# thermostat-2layer-v1.net
KiCad netlist of a schematic drawn in EAGLE
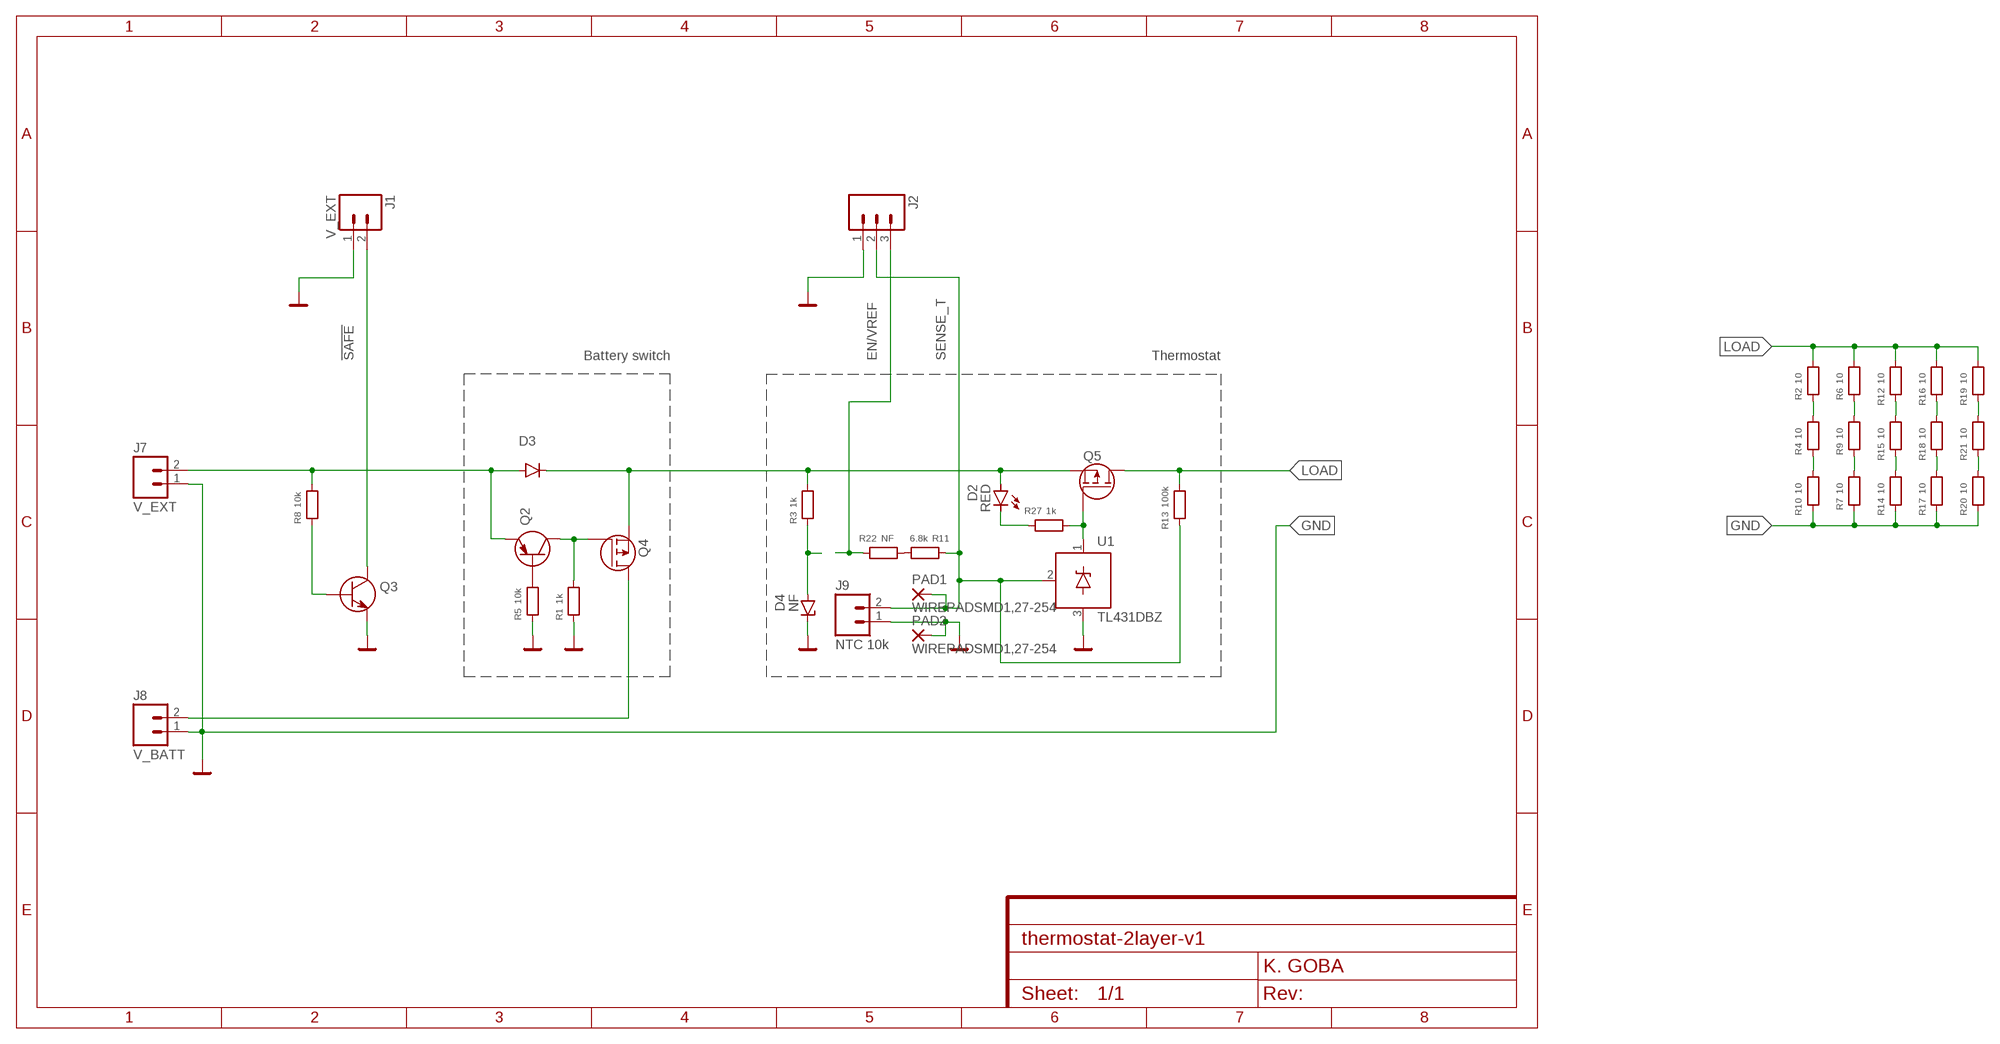
[diagram p0: schematic, sheet 1]

(export (version "E")
  (design (tool "Eeschema 10.0.6"))
  (components
    (comp (ref "D2")
      (value "RED")
      (footprint "eagle-import:R0805")
      (libsource (lib "eagle-import") (part "LED0805"))
    )
    (comp (ref "D3")
      (value "DIODE-SMA-ALT")
      (footprint "eagle-import:D-SMA-ALT")
      (libsource (lib "eagle-import") (part "DIODE-SMA-ALT"))
    )
    (comp (ref "D4")
      (value "NF")
      (footprint "eagle-import:SOD80")
      (libsource (lib "eagle-import") (part "DIODE-ZENER-SOD80"))
    )
    (comp (ref "J1")
      (value "V_EXT")
      (footprint "eagle-import:JST-2-PTH-VERT")
      (libsource (lib "eagle-import") (part "M2-2MM-JST"))
    )
    (comp (ref "J2")
      (value "M3-CT-V")
      (footprint "eagle-import:JST-3-PTH-VERT")
      (libsource (lib "eagle-import") (part "M3-CT-V"))
    )
    (comp (ref "J7")
      (value "V_EXT")
      (footprint "eagle-import:JST-2-PTH-VERT")
      (libsource (lib "eagle-import") (part "M2-2MM-JST"))
    )
    (comp (ref "J8")
      (value "V_BATT")
      (footprint "eagle-import:JST-2-PTH-VERT")
      (libsource (lib "eagle-import") (part "M2-2MM-JST"))
    )
    (comp (ref "J9")
      (value "NTC 10k")
      (footprint "eagle-import:JST-2-PTH-VERT")
      (libsource (lib "eagle-import") (part "M2-2MM-JST"))
    )
    (comp (ref "PAD1")
      (value "WIREPADSMD1,27-254")
      (footprint "eagle-import:SMD1,27-2,54")
      (libsource (lib "eagle-import") (part "WIREPADSMD1,27-254"))
    )
    (comp (ref "PAD2")
      (value "WIREPADSMD1,27-254")
      (footprint "eagle-import:SMD1,27-2,54")
      (libsource (lib "eagle-import") (part "WIREPADSMD1,27-254"))
    )
    (comp (ref "Q2")
      (value "BJT-PNPSMD")
      (footprint "eagle-import:SOT23-3")
      (libsource (lib "eagle-import") (part "BJT-PNPSMD"))
    )
    (comp (ref "Q3")
      (value "BJT-NPN-SOT23-3")
      (footprint "eagle-import:SOT23-3")
      (libsource (lib "eagle-import") (part "BJT-NPN-SOT23-3"))
    )
    (comp (ref "Q4")
      (value "MOSFET-P-SOT23-3")
      (footprint "eagle-import:SOT23-3")
      (libsource (lib "eagle-import") (part "MOSFET-P-SOT23-3"))
    )
    (comp (ref "Q5")
      (value "MOSFET-P-SOT23-3")
      (footprint "eagle-import:SOT23-3")
      (libsource (lib "eagle-import") (part "MOSFET-P-SOT23-3"))
    )
    (comp (ref "R1")
      (value "1k")
      (footprint "eagle-import:R0603")
      (libsource (lib "eagle-import") (part "RESISTOR-0603"))
    )
    (comp (ref "R2")
      (value "10")
      (footprint "eagle-import:R1206")
      (libsource (lib "eagle-import") (part "RESISTOR-1206"))
    )
    (comp (ref "R3")
      (value "1k")
      (footprint "eagle-import:R0603")
      (libsource (lib "eagle-import") (part "RESISTOR-0603"))
    )
    (comp (ref "R4")
      (value "10")
      (footprint "eagle-import:R1206")
      (libsource (lib "eagle-import") (part "RESISTOR-1206"))
    )
    (comp (ref "R5")
      (value "10k")
      (footprint "eagle-import:R0603")
      (libsource (lib "eagle-import") (part "RESISTOR-0603"))
    )
    (comp (ref "R6")
      (value "10")
      (footprint "eagle-import:R1206")
      (libsource (lib "eagle-import") (part "RESISTOR-1206"))
    )
    (comp (ref "R7")
      (value "10")
      (footprint "eagle-import:R1206")
      (libsource (lib "eagle-import") (part "RESISTOR-1206"))
    )
    (comp (ref "R8")
      (value "10k")
      (footprint "eagle-import:R0603")
      (libsource (lib "eagle-import") (part "RESISTOR-0603"))
    )
    (comp (ref "R9")
      (value "10")
      (footprint "eagle-import:R1206")
      (libsource (lib "eagle-import") (part "RESISTOR-1206"))
    )
    (comp (ref "R10")
      (value "10")
      (footprint "eagle-import:R1206")
      (libsource (lib "eagle-import") (part "RESISTOR-1206"))
    )
    (comp (ref "R11")
      (value "6.8k")
      (footprint "eagle-import:R0603")
      (libsource (lib "eagle-import") (part "RESISTOR-0603"))
    )
    (comp (ref "R12")
      (value "10")
      (footprint "eagle-import:R1206")
      (libsource (lib "eagle-import") (part "RESISTOR-1206"))
    )
    (comp (ref "R13")
      (value "100k")
      (footprint "eagle-import:R0603")
      (libsource (lib "eagle-import") (part "RESISTOR-0603"))
    )
    (comp (ref "R14")
      (value "10")
      (footprint "eagle-import:R1206")
      (libsource (lib "eagle-import") (part "RESISTOR-1206"))
    )
    (comp (ref "R15")
      (value "10")
      (footprint "eagle-import:R1206")
      (libsource (lib "eagle-import") (part "RESISTOR-1206"))
    )
    (comp (ref "R16")
      (value "10")
      (footprint "eagle-import:R1206")
      (libsource (lib "eagle-import") (part "RESISTOR-1206"))
    )
    (comp (ref "R17")
      (value "10")
      (footprint "eagle-import:R1206")
      (libsource (lib "eagle-import") (part "RESISTOR-1206"))
    )
    (comp (ref "R18")
      (value "10")
      (footprint "eagle-import:R1206")
      (libsource (lib "eagle-import") (part "RESISTOR-1206"))
    )
    (comp (ref "R19")
      (value "10")
      (footprint "eagle-import:R1206")
      (libsource (lib "eagle-import") (part "RESISTOR-1206"))
    )
    (comp (ref "R20")
      (value "10")
      (footprint "eagle-import:R1206")
      (libsource (lib "eagle-import") (part "RESISTOR-1206"))
    )
    (comp (ref "R21")
      (value "10")
      (footprint "eagle-import:R1206")
      (libsource (lib "eagle-import") (part "RESISTOR-1206"))
    )
    (comp (ref "R22")
      (value "NF")
      (footprint "eagle-import:R0603")
      (libsource (lib "eagle-import") (part "RESISTOR-0603"))
    )
    (comp (ref "R27")
      (value "1k")
      (footprint "eagle-import:R0603")
      (libsource (lib "eagle-import") (part "RESISTOR-0603"))
    )
    (comp (ref "U1")
      (value "TL431DBZ")
      (footprint "eagle-import:SOT23-3")
      (libsource (lib "eagle-import") (part "TL431DBZ"))
    )
  )
  (nets
    (net (code "1") (name "/EN{slash}VREF") (class "Default")
      (node (ref "J2") (pin "3") (pinfunction "3_3") (pintype "passive"))
      (node (ref "R22") (pin "1") (pinfunction "1_1") (pintype "passive"))
    )
    (net (code "2") (name "/SENSE_T") (class "Default")
      (node (ref "J2") (pin "2") (pinfunction "2_2") (pintype "passive"))
      (node (ref "J9") (pin "2") (pinfunction "2_2") (pintype "passive"))
      (node (ref "PAD1") (pin "1") (pinfunction "P_1") (pintype "passive"))
      (node (ref "R11") (pin "1") (pinfunction "1_1") (pintype "passive"))
      (node (ref "R13") (pin "1") (pinfunction "1_1") (pintype "passive"))
      (node (ref "U1") (pin "2") (pinfunction "R_2") (pintype "bidirectional"))
    )
    (net (code "3") (name "/~{SAFE}") (class "Default")
      (node (ref "J1") (pin "2") (pinfunction "2_2") (pintype "passive"))
      (node (ref "Q3") (pin "3") (pinfunction "C_3") (pintype "passive"))
    )
    (net (code "4") (name "GND") (class "Default")
      (node (ref "D4") (pin "C") (pinfunction "C_C") (pintype "passive"))
      (node (ref "J1") (pin "1") (pinfunction "1_1") (pintype "passive"))
      (node (ref "J2") (pin "1") (pinfunction "1_1") (pintype "passive"))
      (node (ref "J7") (pin "1") (pinfunction "1_1") (pintype "passive"))
      (node (ref "J8") (pin "1") (pinfunction "1_1") (pintype "passive"))
      (node (ref "J9") (pin "1") (pinfunction "1_1") (pintype "passive"))
      (node (ref "PAD2") (pin "1") (pinfunction "P_1") (pintype "passive"))
      (node (ref "Q3") (pin "2") (pinfunction "E_2") (pintype "passive"))
      (node (ref "R1") (pin "1") (pinfunction "1_1") (pintype "passive"))
      (node (ref "R10") (pin "1") (pinfunction "1_1") (pintype "passive"))
      (node (ref "R14") (pin "1") (pinfunction "1_1") (pintype "passive"))
      (node (ref "R17") (pin "1") (pinfunction "1_1") (pintype "passive"))
      (node (ref "R20") (pin "1") (pinfunction "1_1") (pintype "passive"))
      (node (ref "R5") (pin "1") (pinfunction "1_1") (pintype "passive"))
      (node (ref "R7") (pin "1") (pinfunction "1_1") (pintype "passive"))
      (node (ref "U1") (pin "3") (pinfunction "A_3") (pintype "bidirectional"))
    )
    (net (code "5") (name "LOAD") (class "Default")
      (node (ref "Q5") (pin "3") (pinfunction "D_3") (pintype "passive"))
      (node (ref "R12") (pin "2") (pinfunction "2_2") (pintype "passive"))
      (node (ref "R13") (pin "2") (pinfunction "2_2") (pintype "passive"))
      (node (ref "R16") (pin "2") (pinfunction "2_2") (pintype "passive"))
      (node (ref "R19") (pin "2") (pinfunction "2_2") (pintype "passive"))
      (node (ref "R2") (pin "2") (pinfunction "2_2") (pintype "passive"))
      (node (ref "R6") (pin "2") (pinfunction "2_2") (pintype "passive"))
    )
    (net (code "6") (name "Net-(D2-A)") (class "Default")
      (node (ref "D2") (pin "1") (pinfunction "A_1") (pintype "passive"))
      (node (ref "D3") (pin "C") (pinfunction "C_C") (pintype "passive"))
      (node (ref "Q4") (pin "2") (pinfunction "S_2") (pintype "passive"))
      (node (ref "Q5") (pin "2") (pinfunction "S_2") (pintype "passive"))
      (node (ref "R3") (pin "2") (pinfunction "2_2") (pintype "passive"))
    )
    (net (code "7") (name "Net-(D2-C)") (class "Default")
      (node (ref "D2") (pin "2") (pinfunction "C_2") (pintype "passive"))
      (node (ref "R27") (pin "1") (pinfunction "1_1") (pintype "passive"))
    )
    (net (code "8") (name "Net-(D4-PadA)") (class "Default")
      (node (ref "D4") (pin "A") (pinfunction "A_A") (pintype "passive"))
      (node (ref "R3") (pin "1") (pinfunction "1_1") (pintype "passive"))
    )
    (net (code "9") (name "Net-(Q2-B)") (class "Default")
      (node (ref "Q2") (pin "1") (pinfunction "B_1") (pintype "passive"))
      (node (ref "R5") (pin "2") (pinfunction "2_2") (pintype "passive"))
    )
    (net (code "10") (name "Net-(Q2-C)") (class "Default")
      (node (ref "Q2") (pin "3") (pinfunction "C_3") (pintype "passive"))
      (node (ref "Q4") (pin "1") (pinfunction "G_1") (pintype "passive"))
      (node (ref "R1") (pin "2") (pinfunction "2_2") (pintype "passive"))
    )
    (net (code "11") (name "Net-(Q2-E)") (class "Default")
      (node (ref "D3") (pin "A") (pinfunction "A_A") (pintype "passive"))
      (node (ref "J7") (pin "2") (pinfunction "2_2") (pintype "passive"))
      (node (ref "Q2") (pin "2") (pinfunction "E_2") (pintype "passive"))
      (node (ref "R8") (pin "2") (pinfunction "2_2") (pintype "passive"))
    )
    (net (code "12") (name "Net-(Q3-B)") (class "Default")
      (node (ref "Q3") (pin "1") (pinfunction "B_1") (pintype "passive"))
      (node (ref "R8") (pin "1") (pinfunction "1_1") (pintype "passive"))
    )
    (net (code "13") (name "Net-(Q4-D)") (class "Default")
      (node (ref "J8") (pin "2") (pinfunction "2_2") (pintype "passive"))
      (node (ref "Q4") (pin "3") (pinfunction "D_3") (pintype "passive"))
    )
    (net (code "14") (name "Net-(Q5-G)") (class "Default")
      (node (ref "Q5") (pin "1") (pinfunction "G_1") (pintype "passive"))
      (node (ref "R27") (pin "2") (pinfunction "2_2") (pintype "passive"))
      (node (ref "U1") (pin "1") (pinfunction "C_1") (pintype "bidirectional"))
    )
    (net (code "15") (name "Net-(R2-Pad1)") (class "Default")
      (node (ref "R2") (pin "1") (pinfunction "1_1") (pintype "passive"))
      (node (ref "R4") (pin "2") (pinfunction "2_2") (pintype "passive"))
    )
    (net (code "16") (name "Net-(R6-Pad1)") (class "Default")
      (node (ref "R6") (pin "1") (pinfunction "1_1") (pintype "passive"))
      (node (ref "R9") (pin "2") (pinfunction "2_2") (pintype "passive"))
    )
    (net (code "17") (name "Net-(R7-Pad2)") (class "Default")
      (node (ref "R7") (pin "2") (pinfunction "2_2") (pintype "passive"))
      (node (ref "R9") (pin "1") (pinfunction "1_1") (pintype "passive"))
    )
    (net (code "18") (name "Net-(R10-Pad2)") (class "Default")
      (node (ref "R10") (pin "2") (pinfunction "2_2") (pintype "passive"))
      (node (ref "R4") (pin "1") (pinfunction "1_1") (pintype "passive"))
    )
    (net (code "19") (name "Net-(R11-Pad2)") (class "Default")
      (node (ref "R11") (pin "2") (pinfunction "2_2") (pintype "passive"))
      (node (ref "R22") (pin "2") (pinfunction "2_2") (pintype "passive"))
    )
    (net (code "20") (name "Net-(R12-Pad1)") (class "Default")
      (node (ref "R12") (pin "1") (pinfunction "1_1") (pintype "passive"))
      (node (ref "R15") (pin "2") (pinfunction "2_2") (pintype "passive"))
    )
    (net (code "21") (name "Net-(R14-Pad2)") (class "Default")
      (node (ref "R14") (pin "2") (pinfunction "2_2") (pintype "passive"))
      (node (ref "R15") (pin "1") (pinfunction "1_1") (pintype "passive"))
    )
    (net (code "22") (name "Net-(R16-Pad1)") (class "Default")
      (node (ref "R16") (pin "1") (pinfunction "1_1") (pintype "passive"))
      (node (ref "R18") (pin "2") (pinfunction "2_2") (pintype "passive"))
    )
    (net (code "23") (name "Net-(R17-Pad2)") (class "Default")
      (node (ref "R17") (pin "2") (pinfunction "2_2") (pintype "passive"))
      (node (ref "R18") (pin "1") (pinfunction "1_1") (pintype "passive"))
    )
    (net (code "24") (name "Net-(R19-Pad1)") (class "Default")
      (node (ref "R19") (pin "1") (pinfunction "1_1") (pintype "passive"))
      (node (ref "R21") (pin "2") (pinfunction "2_2") (pintype "passive"))
    )
    (net (code "25") (name "Net-(R20-Pad2)") (class "Default")
      (node (ref "R20") (pin "2") (pinfunction "2_2") (pintype "passive"))
      (node (ref "R21") (pin "1") (pinfunction "1_1") (pintype "passive"))
    )
  )
)
